# MRCS-ODX4_v17a.net
KiCad netlist of a schematic drawn in EAGLE
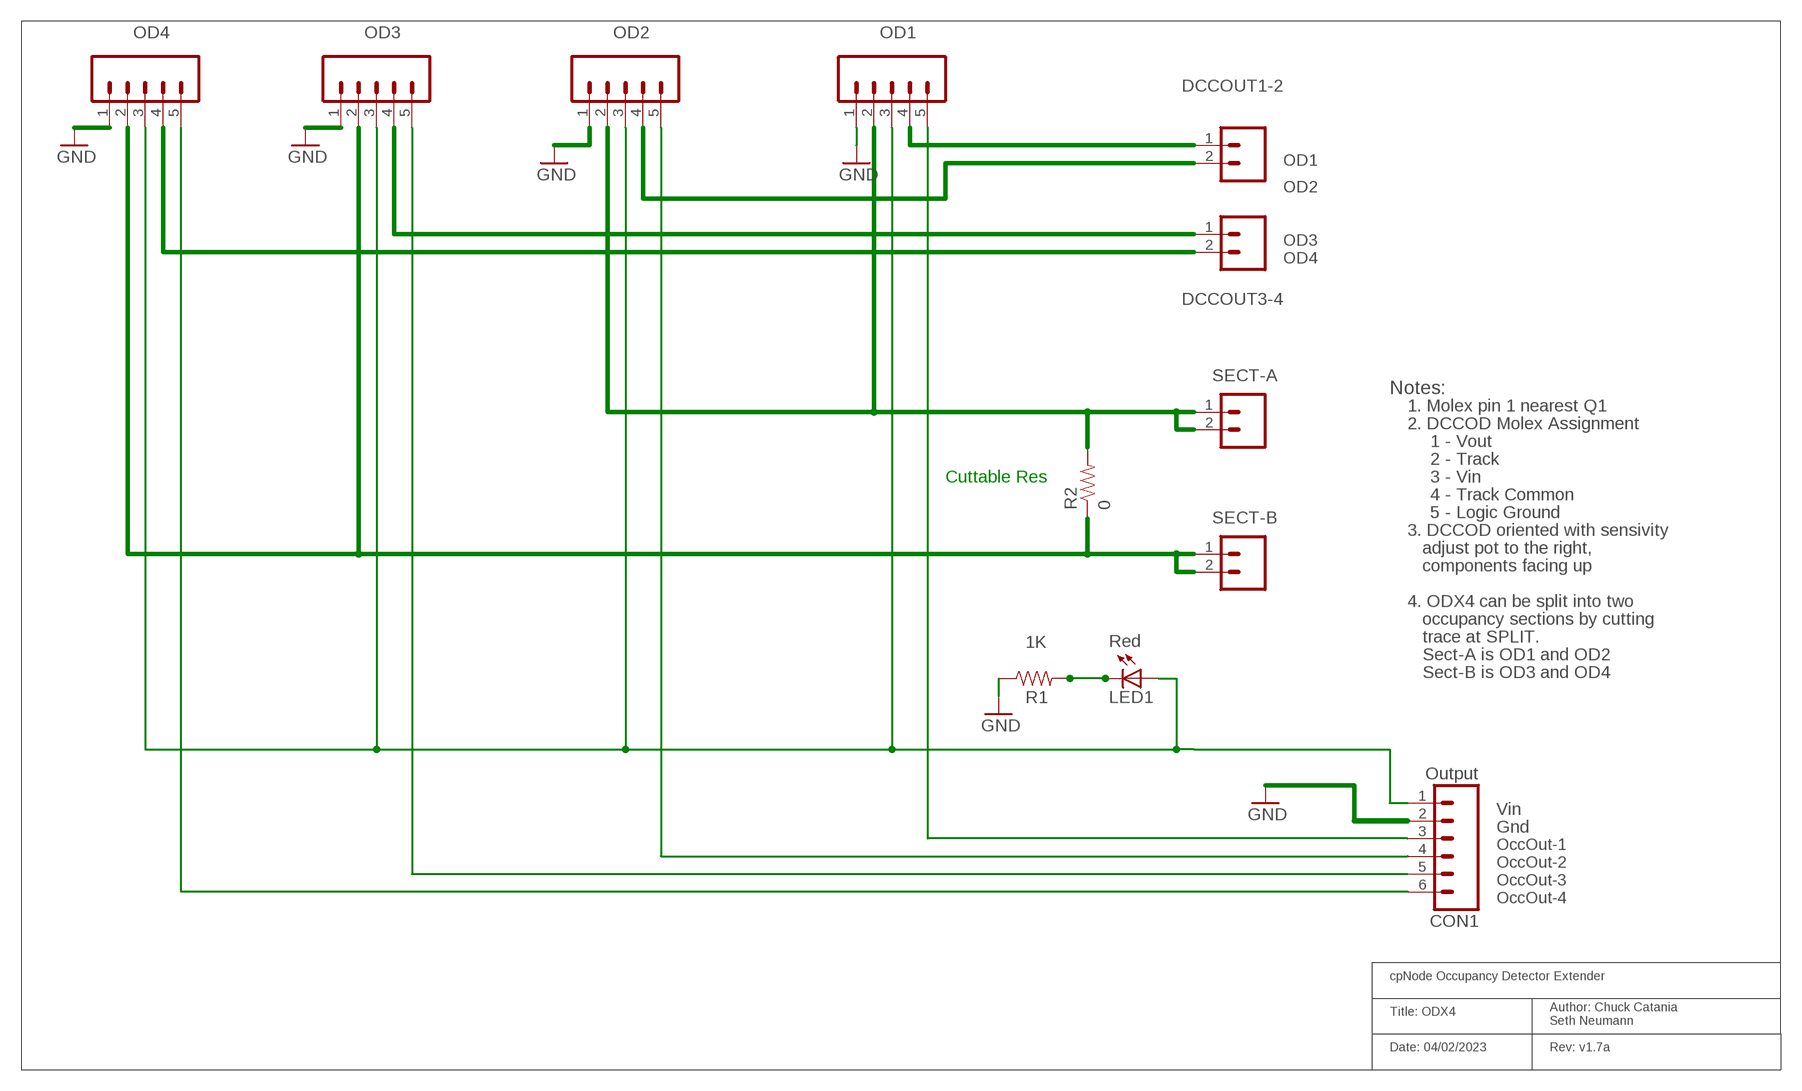
[diagram p0: schematic, sheet 1]

(export (version "E")
  (design (tool "Eeschema 10.0.6"))
  (components
    (comp (ref "CON1")
      (value "Output")
      (footprint "eagle-import:MOLEX-1X6_LOCK")
      (libsource (lib "eagle-import") (part "CONNECTOR-M06POLAR_LOCK"))
    )
    (comp (ref "DCCOUT1-2")
      (value "CONNECTOR-M025MM-LOCK")
      (footprint "eagle-import:SCREWTERMINAL-5MM-2")
      (libsource (lib "eagle-import") (part "CONNECTOR-M025MM-LOCK"))
    )
    (comp (ref "DCCOUT3-4")
      (value "CONNECTOR-M025MM-LOCK")
      (footprint "eagle-import:SCREWTERMINAL-5MM-2")
      (libsource (lib "eagle-import") (part "CONNECTOR-M025MM-LOCK"))
    )
    (comp (ref "LED1")
      (value "Red")
      (footprint "eagle-import:LED3MM")
      (libsource (lib "eagle-import") (part "LEDLED3MM"))
    )
    (comp (ref "OD1")
      (value "CONNECTOR-M051.56")
      (footprint "eagle-import:KK-156-5")
      (libsource (lib "eagle-import") (part "CONNECTOR-M051.56"))
    )
    (comp (ref "OD2")
      (value "CONNECTOR-M051.56")
      (footprint "eagle-import:KK-156-5")
      (libsource (lib "eagle-import") (part "CONNECTOR-M051.56"))
    )
    (comp (ref "OD3")
      (value "CONNECTOR-M051.56")
      (footprint "eagle-import:KK-156-5")
      (libsource (lib "eagle-import") (part "CONNECTOR-M051.56"))
    )
    (comp (ref "OD4")
      (value "CONNECTOR-M051.56")
      (footprint "eagle-import:KK-156-5")
      (libsource (lib "eagle-import") (part "CONNECTOR-M051.56"))
    )
    (comp (ref "R1")
      (value "1K")
      (footprint "eagle-import:AXIAL-0.4-RES")
      (libsource (lib "eagle-import") (part "RPTH04"))
    )
    (comp (ref "R2")
      (value "0")
      (footprint "eagle-import:CUT-R")
      (libsource (lib "eagle-import") (part "RPTH-R0"))
    )
    (comp (ref "SECT-A")
      (value "M025MM")
      (footprint "eagle-import:SCREWTERMINAL-5MM-2")
      (libsource (lib "eagle-import") (part "M025MM"))
    )
    (comp (ref "SECT-B")
      (value "M025MM")
      (footprint "eagle-import:SCREWTERMINAL-5MM-2")
      (libsource (lib "eagle-import") (part "M025MM"))
    )
  )
  (nets
    (net (code "1") (name "GND") (class "Default")
      (node (ref "CON1") (pin "2") (pinfunction "2_2") (pintype "passive"))
      (node (ref "OD1") (pin "1") (pinfunction "1_1") (pintype "passive"))
      (node (ref "OD2") (pin "1") (pinfunction "1_1") (pintype "passive"))
      (node (ref "OD3") (pin "1") (pinfunction "1_1") (pintype "passive"))
      (node (ref "OD4") (pin "1") (pinfunction "1_1") (pintype "passive"))
      (node (ref "R1") (pin "P$1") (pinfunction "1_P$1") (pintype "passive"))
    )
    (net (code "2") (name "Net-(CON1-Pad1)") (class "Default")
      (node (ref "CON1") (pin "1") (pinfunction "1_1") (pintype "passive"))
      (node (ref "LED1") (pin "A") (pinfunction "A_A") (pintype "passive"))
      (node (ref "OD1") (pin "3") (pinfunction "3_3") (pintype "passive"))
      (node (ref "OD2") (pin "3") (pinfunction "3_3") (pintype "passive"))
      (node (ref "OD3") (pin "3") (pinfunction "3_3") (pintype "passive"))
      (node (ref "OD4") (pin "3") (pinfunction "3_3") (pintype "passive"))
    )
    (net (code "3") (name "Net-(CON1-Pad3)") (class "Default")
      (node (ref "CON1") (pin "3") (pinfunction "3_3") (pintype "passive"))
      (node (ref "OD1") (pin "5") (pinfunction "5_5") (pintype "passive"))
    )
    (net (code "4") (name "Net-(CON1-Pad4)") (class "Default")
      (node (ref "CON1") (pin "4") (pinfunction "4_4") (pintype "passive"))
      (node (ref "OD2") (pin "5") (pinfunction "5_5") (pintype "passive"))
    )
    (net (code "5") (name "Net-(CON1-Pad5)") (class "Default")
      (node (ref "CON1") (pin "5") (pinfunction "5_5") (pintype "passive"))
      (node (ref "OD3") (pin "5") (pinfunction "5_5") (pintype "passive"))
    )
    (net (code "6") (name "Net-(CON1-Pad6)") (class "Default")
      (node (ref "CON1") (pin "6") (pinfunction "6_6") (pintype "passive"))
      (node (ref "OD4") (pin "5") (pinfunction "5_5") (pintype "passive"))
    )
    (net (code "7") (name "Net-(DCCOUT1-2-A)") (class "Default")
      (node (ref "DCCOUT1-2") (pin "1") (pinfunction "A_1") (pintype "passive"))
      (node (ref "OD1") (pin "4") (pinfunction "4_4") (pintype "passive"))
    )
    (net (code "8") (name "Net-(DCCOUT1-2-B)") (class "Default")
      (node (ref "DCCOUT1-2") (pin "2") (pinfunction "B_2") (pintype "passive"))
      (node (ref "OD2") (pin "4") (pinfunction "4_4") (pintype "passive"))
    )
    (net (code "9") (name "Net-(DCCOUT3-4-A)") (class "Default")
      (node (ref "DCCOUT3-4") (pin "1") (pinfunction "A_1") (pintype "passive"))
      (node (ref "OD3") (pin "4") (pinfunction "4_4") (pintype "passive"))
    )
    (net (code "10") (name "Net-(DCCOUT3-4-B)") (class "Default")
      (node (ref "DCCOUT3-4") (pin "2") (pinfunction "B_2") (pintype "passive"))
      (node (ref "OD4") (pin "4") (pinfunction "4_4") (pintype "passive"))
    )
    (net (code "11") (name "Net-(LED1-C)") (class "Default")
      (node (ref "LED1") (pin "K") (pinfunction "C_K") (pintype "passive"))
      (node (ref "R1") (pin "P$2") (pinfunction "2_P$2") (pintype "passive"))
    )
    (net (code "12") (name "Net-(R2-1)") (class "Default")
      (node (ref "OD3") (pin "2") (pinfunction "2_2") (pintype "passive"))
      (node (ref "OD4") (pin "2") (pinfunction "2_2") (pintype "passive"))
      (node (ref "R2") (pin "P2") (pinfunction "1_P2") (pintype "passive"))
      (node (ref "SECT-B") (pin "1") (pinfunction "1_1") (pintype "passive"))
      (node (ref "SECT-B") (pin "2") (pinfunction "2_2") (pintype "passive"))
    )
    (net (code "13") (name "Net-(R2-2)") (class "Default")
      (node (ref "OD1") (pin "2") (pinfunction "2_2") (pintype "passive"))
      (node (ref "OD2") (pin "2") (pinfunction "2_2") (pintype "passive"))
      (node (ref "R2") (pin "P1") (pinfunction "2_P1") (pintype "passive"))
      (node (ref "SECT-A") (pin "1") (pinfunction "1_1") (pintype "passive"))
      (node (ref "SECT-A") (pin "2") (pinfunction "2_2") (pintype "passive"))
    )
  )
)
